# SevenSegment.net
KiCad netlist of a schematic drawn in Altium Designer
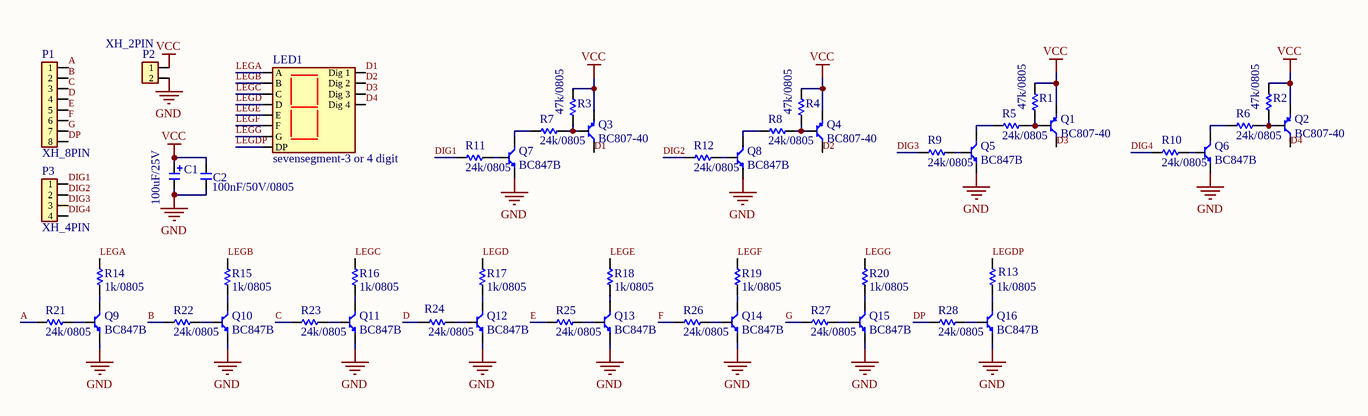
[diagram p0: SevenSegment.SchDoc]

(export (version "E")
  (design (tool "Eeschema 10.0.6"))
  (components
    (comp (ref "C1")
      (value "100uF/25V")
      (footprint "100uF/25V")
      (libsource (lib "SCHAM_LIB") (part "Capacitor-pol"))
    )
    (comp (ref "C2")
      (value "100nF/50V/0805")
      (footprint "Capacitor 0805")
      (libsource (lib "SCHAM_LIB") (part "capacitor"))
    )
    (comp (ref "LED1")
      (value "sevensegment-3 or 4 digit")
      (footprint "5631BS-7SEG")
      (libsource (lib "SCHAM_LIB") (part "sevensegment-3 or 4 digit"))
    )
    (comp (ref "P1")
      (value "XH_8PIN")
      (footprint "pin-header 8*1")
      (libsource (lib "SCHAM_LIB") (part "header 8pin"))
    )
    (comp (ref "P2")
      (value "XH_2PIN")
      (footprint "pin-header 2*1")
      (libsource (lib "SCHAM_LIB") (part "header 2pin"))
    )
    (comp (ref "P3")
      (value "XH_4PIN")
      (footprint "pin-header 4*1")
      (libsource (lib "SCHAM_LIB") (part "header 4pin"))
    )
    (comp (ref "Q1") (value "BC807-40") (footprint "SOT23") (libsource (lib "SCHAM_LIB") (part "bjt-pnp")))
    (comp (ref "Q2") (value "BC807-40") (footprint "SOT23") (libsource (lib "SCHAM_LIB") (part "bjt-pnp")))
    (comp (ref "Q3") (value "BC807-40") (footprint "SOT23") (libsource (lib "SCHAM_LIB") (part "bjt-pnp")))
    (comp (ref "Q4") (value "BC807-40") (footprint "SOT23") (libsource (lib "SCHAM_LIB") (part "bjt-pnp")))
    (comp (ref "Q5") (value "BC847B") (footprint "SOT23") (libsource (lib "SCHAM_LIB") (part "bjt-npn")))
    (comp (ref "Q6") (value "BC847B") (footprint "SOT23") (libsource (lib "SCHAM_LIB") (part "bjt-npn")))
    (comp (ref "Q7") (value "BC847B") (footprint "SOT23") (libsource (lib "SCHAM_LIB") (part "bjt-npn")))
    (comp (ref "Q8") (value "BC847B") (footprint "SOT23") (libsource (lib "SCHAM_LIB") (part "bjt-npn")))
    (comp (ref "Q9") (value "BC847B") (footprint "SOT23") (libsource (lib "SCHAM_LIB") (part "bjt-npn")))
    (comp (ref "Q10") (value "BC847B") (footprint "SOT23") (libsource (lib "SCHAM_LIB") (part "bjt-npn")))
    (comp (ref "Q11") (value "BC847B") (footprint "SOT23") (libsource (lib "SCHAM_LIB") (part "bjt-npn")))
    (comp (ref "Q12") (value "BC847B") (footprint "SOT23") (libsource (lib "SCHAM_LIB") (part "bjt-npn")))
    (comp (ref "Q13") (value "BC847B") (footprint "SOT23") (libsource (lib "SCHAM_LIB") (part "bjt-npn")))
    (comp (ref "Q14") (value "BC847B") (footprint "SOT23") (libsource (lib "SCHAM_LIB") (part "bjt-npn")))
    (comp (ref "Q15") (value "BC847B") (footprint "SOT23") (libsource (lib "SCHAM_LIB") (part "bjt-npn")))
    (comp (ref "Q16") (value "BC847B") (footprint "SOT23") (libsource (lib "SCHAM_LIB") (part "bjt-npn")))
    (comp (ref "R1")
      (value "47k/0805")
      (footprint "Resistor 0805")
      (libsource (lib "SCHAM_LIB") (part "resistor"))
    )
    (comp (ref "R2")
      (value "47k/0805")
      (footprint "Resistor 0805")
      (libsource (lib "SCHAM_LIB") (part "resistor"))
    )
    (comp (ref "R3")
      (value "47k/0805")
      (footprint "Resistor 0805")
      (libsource (lib "SCHAM_LIB") (part "resistor"))
    )
    (comp (ref "R4")
      (value "47k/0805")
      (footprint "Resistor 0805")
      (libsource (lib "SCHAM_LIB") (part "resistor"))
    )
    (comp (ref "R5")
      (value "24k/0805")
      (footprint "Resistor 0805")
      (libsource (lib "SCHAM_LIB") (part "resistor"))
    )
    (comp (ref "R6")
      (value "24k/0805")
      (footprint "Resistor 0805")
      (libsource (lib "SCHAM_LIB") (part "resistor"))
    )
    (comp (ref "R7")
      (value "24k/0805")
      (footprint "Resistor 0805")
      (libsource (lib "SCHAM_LIB") (part "resistor"))
    )
    (comp (ref "R8")
      (value "24k/0805")
      (footprint "Resistor 0805")
      (libsource (lib "SCHAM_LIB") (part "resistor"))
    )
    (comp (ref "R9")
      (value "24k/0805")
      (footprint "Resistor 0805")
      (libsource (lib "SCHAM_LIB") (part "resistor"))
    )
    (comp (ref "R10")
      (value "24k/0805")
      (footprint "Resistor 0805")
      (libsource (lib "SCHAM_LIB") (part "resistor"))
    )
    (comp (ref "R11")
      (value "24k/0805")
      (footprint "Resistor 0805")
      (libsource (lib "SCHAM_LIB") (part "resistor"))
    )
    (comp (ref "R12")
      (value "24k/0805")
      (footprint "Resistor 0805")
      (libsource (lib "SCHAM_LIB") (part "resistor"))
    )
    (comp (ref "R13")
      (value "1k/0805")
      (footprint "Resistor 0805")
      (libsource (lib "SCHAM_LIB") (part "resistor"))
    )
    (comp (ref "R14")
      (value "1k/0805")
      (footprint "Resistor 0805")
      (libsource (lib "SCHAM_LIB") (part "resistor"))
    )
    (comp (ref "R15")
      (value "1k/0805")
      (footprint "Resistor 0805")
      (libsource (lib "SCHAM_LIB") (part "resistor"))
    )
    (comp (ref "R16")
      (value "1k/0805")
      (footprint "Resistor 0805")
      (libsource (lib "SCHAM_LIB") (part "resistor"))
    )
    (comp (ref "R17")
      (value "1k/0805")
      (footprint "Resistor 0805")
      (libsource (lib "SCHAM_LIB") (part "resistor"))
    )
    (comp (ref "R18")
      (value "1k/0805")
      (footprint "Resistor 0805")
      (libsource (lib "SCHAM_LIB") (part "resistor"))
    )
    (comp (ref "R19")
      (value "1k/0805")
      (footprint "Resistor 0805")
      (libsource (lib "SCHAM_LIB") (part "resistor"))
    )
    (comp (ref "R20")
      (value "1k/0805")
      (footprint "Resistor 0805")
      (libsource (lib "SCHAM_LIB") (part "resistor"))
    )
    (comp (ref "R21")
      (value "24k/0805")
      (footprint "Resistor 0805")
      (libsource (lib "SCHAM_LIB") (part "resistor"))
    )
    (comp (ref "R22")
      (value "24k/0805")
      (footprint "Resistor 0805")
      (libsource (lib "SCHAM_LIB") (part "resistor"))
    )
    (comp (ref "R23")
      (value "24k/0805")
      (footprint "Resistor 0805")
      (libsource (lib "SCHAM_LIB") (part "resistor"))
    )
    (comp (ref "R24")
      (value "24k/0805")
      (footprint "Resistor 0805")
      (libsource (lib "SCHAM_LIB") (part "resistor"))
    )
    (comp (ref "R25")
      (value "24k/0805")
      (footprint "Resistor 0805")
      (libsource (lib "SCHAM_LIB") (part "resistor"))
    )
    (comp (ref "R26")
      (value "24k/0805")
      (footprint "Resistor 0805")
      (libsource (lib "SCHAM_LIB") (part "resistor"))
    )
    (comp (ref "R27")
      (value "24k/0805")
      (footprint "Resistor 0805")
      (libsource (lib "SCHAM_LIB") (part "resistor"))
    )
    (comp (ref "R28")
      (value "24k/0805")
      (footprint "Resistor 0805")
      (libsource (lib "SCHAM_LIB") (part "resistor"))
    )
  )
  (nets
    (net (code "1") (name "/A") (class "Default")
      (node (ref "P1") (pin "1") (pinfunction "1_1") (pintype "passive"))
      (node (ref "R21") (pin "2") (pinfunction "2_2") (pintype "passive"))
    )
    (net (code "2") (name "/B") (class "Default")
      (node (ref "P1") (pin "2") (pinfunction "2_2") (pintype "passive"))
      (node (ref "R22") (pin "2") (pinfunction "2_2") (pintype "passive"))
    )
    (net (code "3") (name "/C") (class "Default")
      (node (ref "P1") (pin "3") (pinfunction "3_3") (pintype "passive"))
      (node (ref "R23") (pin "2") (pinfunction "2_2") (pintype "passive"))
    )
    (net (code "4") (name "/D") (class "Default")
      (node (ref "P1") (pin "4") (pinfunction "4_4") (pintype "passive"))
      (node (ref "R24") (pin "2") (pinfunction "2_2") (pintype "passive"))
    )
    (net (code "5") (name "/D1") (class "Default")
      (node (ref "LED1") (pin "12") (pinfunction "Dig_1_12") (pintype "passive"))
      (node (ref "Q3") (pin "3") (pinfunction "C_3") (pintype "passive"))
    )
    (net (code "6") (name "/D2") (class "Default")
      (node (ref "LED1") (pin "9") (pinfunction "Dig_2_9") (pintype "passive"))
      (node (ref "Q4") (pin "3") (pinfunction "C_3") (pintype "passive"))
    )
    (net (code "7") (name "/D3") (class "Default")
      (node (ref "LED1") (pin "8") (pinfunction "Dig_3_8") (pintype "passive"))
      (node (ref "Q1") (pin "3") (pinfunction "C_3") (pintype "passive"))
    )
    (net (code "8") (name "/D4") (class "Default")
      (node (ref "LED1") (pin "6") (pinfunction "Dig_4_6") (pintype "passive"))
      (node (ref "Q2") (pin "3") (pinfunction "C_3") (pintype "passive"))
    )
    (net (code "9") (name "/DIG1") (class "Default")
      (node (ref "P3") (pin "1") (pinfunction "1_1") (pintype "passive"))
      (node (ref "R11") (pin "2") (pinfunction "2_2") (pintype "passive"))
    )
    (net (code "10") (name "/DIG2") (class "Default")
      (node (ref "P3") (pin "2") (pinfunction "2_2") (pintype "passive"))
      (node (ref "R12") (pin "2") (pinfunction "2_2") (pintype "passive"))
    )
    (net (code "11") (name "/DIG3") (class "Default")
      (node (ref "P3") (pin "3") (pinfunction "3_3") (pintype "passive"))
      (node (ref "R9") (pin "2") (pinfunction "2_2") (pintype "passive"))
    )
    (net (code "12") (name "/DIG4") (class "Default")
      (node (ref "P3") (pin "4") (pinfunction "4_4") (pintype "passive"))
      (node (ref "R10") (pin "2") (pinfunction "2_2") (pintype "passive"))
    )
    (net (code "13") (name "/DP") (class "Default")
      (node (ref "P1") (pin "8") (pinfunction "8_8") (pintype "passive"))
      (node (ref "R28") (pin "2") (pinfunction "2_2") (pintype "passive"))
    )
    (net (code "14") (name "/E") (class "Default")
      (node (ref "P1") (pin "5") (pinfunction "5_5") (pintype "passive"))
      (node (ref "R25") (pin "2") (pinfunction "2_2") (pintype "passive"))
    )
    (net (code "15") (name "/F") (class "Default")
      (node (ref "P1") (pin "6") (pinfunction "6_6") (pintype "passive"))
      (node (ref "R26") (pin "2") (pinfunction "2_2") (pintype "passive"))
    )
    (net (code "16") (name "/G") (class "Default")
      (node (ref "P1") (pin "7") (pinfunction "7_7") (pintype "passive"))
      (node (ref "R27") (pin "2") (pinfunction "2_2") (pintype "passive"))
    )
    (net (code "17") (name "/LEGA") (class "Default")
      (node (ref "LED1") (pin "11") (pinfunction "A_11") (pintype "passive"))
      (node (ref "R14") (pin "1") (pinfunction "1_1") (pintype "passive"))
    )
    (net (code "18") (name "/LEGB") (class "Default")
      (node (ref "LED1") (pin "7") (pinfunction "B_7") (pintype "passive"))
      (node (ref "R15") (pin "1") (pinfunction "1_1") (pintype "passive"))
    )
    (net (code "19") (name "/LEGC") (class "Default")
      (node (ref "LED1") (pin "4") (pinfunction "C_4") (pintype "passive"))
      (node (ref "R16") (pin "1") (pinfunction "1_1") (pintype "passive"))
    )
    (net (code "20") (name "/LEGD") (class "Default")
      (node (ref "LED1") (pin "2") (pinfunction "D_2") (pintype "passive"))
      (node (ref "R17") (pin "1") (pinfunction "1_1") (pintype "passive"))
    )
    (net (code "21") (name "/LEGDP") (class "Default")
      (node (ref "LED1") (pin "3") (pinfunction "DP_3") (pintype "passive"))
      (node (ref "R13") (pin "1") (pinfunction "1_1") (pintype "passive"))
    )
    (net (code "22") (name "/LEGE") (class "Default")
      (node (ref "LED1") (pin "1") (pinfunction "E_1") (pintype "passive"))
      (node (ref "R18") (pin "1") (pinfunction "1_1") (pintype "passive"))
    )
    (net (code "23") (name "/LEGF") (class "Default")
      (node (ref "LED1") (pin "10") (pinfunction "F_10") (pintype "passive"))
      (node (ref "R19") (pin "1") (pinfunction "1_1") (pintype "passive"))
    )
    (net (code "24") (name "/LEGG") (class "Default")
      (node (ref "LED1") (pin "5") (pinfunction "G_5") (pintype "passive"))
      (node (ref "R20") (pin "1") (pinfunction "1_1") (pintype "passive"))
    )
    (net (code "25") (name "GND") (class "Default")
      (node (ref "C1") (pin "2") (pinfunction "2_2") (pintype "passive"))
      (node (ref "C2") (pin "1") (pinfunction "1_1") (pintype "passive"))
      (node (ref "P2") (pin "2") (pinfunction "2_2") (pintype "passive"))
      (node (ref "Q10") (pin "2") (pinfunction "E_2") (pintype "passive"))
      (node (ref "Q11") (pin "2") (pinfunction "E_2") (pintype "passive"))
      (node (ref "Q12") (pin "2") (pinfunction "E_2") (pintype "passive"))
      (node (ref "Q13") (pin "2") (pinfunction "E_2") (pintype "passive"))
      (node (ref "Q14") (pin "2") (pinfunction "E_2") (pintype "passive"))
      (node (ref "Q15") (pin "2") (pinfunction "E_2") (pintype "passive"))
      (node (ref "Q16") (pin "2") (pinfunction "E_2") (pintype "passive"))
      (node (ref "Q5") (pin "2") (pinfunction "E_2") (pintype "passive"))
      (node (ref "Q6") (pin "2") (pinfunction "E_2") (pintype "passive"))
      (node (ref "Q7") (pin "2") (pinfunction "E_2") (pintype "passive"))
      (node (ref "Q8") (pin "2") (pinfunction "E_2") (pintype "passive"))
      (node (ref "Q9") (pin "2") (pinfunction "E_2") (pintype "passive"))
    )
    (net (code "26") (name "Net-(Q1-B)") (class "Default")
      (node (ref "Q1") (pin "1") (pinfunction "B_1") (pintype "passive"))
      (node (ref "R1") (pin "1") (pinfunction "1_1") (pintype "passive"))
      (node (ref "R5") (pin "2") (pinfunction "2_2") (pintype "passive"))
    )
    (net (code "27") (name "Net-(Q2-B)") (class "Default")
      (node (ref "Q2") (pin "1") (pinfunction "B_1") (pintype "passive"))
      (node (ref "R2") (pin "1") (pinfunction "1_1") (pintype "passive"))
      (node (ref "R6") (pin "2") (pinfunction "2_2") (pintype "passive"))
    )
    (net (code "28") (name "Net-(Q3-B)") (class "Default")
      (node (ref "Q3") (pin "1") (pinfunction "B_1") (pintype "passive"))
      (node (ref "R3") (pin "1") (pinfunction "1_1") (pintype "passive"))
      (node (ref "R7") (pin "2") (pinfunction "2_2") (pintype "passive"))
    )
    (net (code "29") (name "Net-(Q4-B)") (class "Default")
      (node (ref "Q4") (pin "1") (pinfunction "B_1") (pintype "passive"))
      (node (ref "R4") (pin "1") (pinfunction "1_1") (pintype "passive"))
      (node (ref "R8") (pin "2") (pinfunction "2_2") (pintype "passive"))
    )
    (net (code "30") (name "Net-(Q5-B)") (class "Default")
      (node (ref "Q5") (pin "1") (pinfunction "B_1") (pintype "passive"))
      (node (ref "R9") (pin "1") (pinfunction "1_1") (pintype "passive"))
    )
    (net (code "31") (name "Net-(Q5-C)") (class "Default")
      (node (ref "Q5") (pin "3") (pinfunction "C_3") (pintype "passive"))
      (node (ref "R5") (pin "1") (pinfunction "1_1") (pintype "passive"))
    )
    (net (code "32") (name "Net-(Q6-B)") (class "Default")
      (node (ref "Q6") (pin "1") (pinfunction "B_1") (pintype "passive"))
      (node (ref "R10") (pin "1") (pinfunction "1_1") (pintype "passive"))
    )
    (net (code "33") (name "Net-(Q6-C)") (class "Default")
      (node (ref "Q6") (pin "3") (pinfunction "C_3") (pintype "passive"))
      (node (ref "R6") (pin "1") (pinfunction "1_1") (pintype "passive"))
    )
    (net (code "34") (name "Net-(Q7-B)") (class "Default")
      (node (ref "Q7") (pin "1") (pinfunction "B_1") (pintype "passive"))
      (node (ref "R11") (pin "1") (pinfunction "1_1") (pintype "passive"))
    )
    (net (code "35") (name "Net-(Q7-C)") (class "Default")
      (node (ref "Q7") (pin "3") (pinfunction "C_3") (pintype "passive"))
      (node (ref "R7") (pin "1") (pinfunction "1_1") (pintype "passive"))
    )
    (net (code "36") (name "Net-(Q8-B)") (class "Default")
      (node (ref "Q8") (pin "1") (pinfunction "B_1") (pintype "passive"))
      (node (ref "R12") (pin "1") (pinfunction "1_1") (pintype "passive"))
    )
    (net (code "37") (name "Net-(Q8-C)") (class "Default")
      (node (ref "Q8") (pin "3") (pinfunction "C_3") (pintype "passive"))
      (node (ref "R8") (pin "1") (pinfunction "1_1") (pintype "passive"))
    )
    (net (code "38") (name "Net-(Q9-B)") (class "Default")
      (node (ref "Q9") (pin "1") (pinfunction "B_1") (pintype "passive"))
      (node (ref "R21") (pin "1") (pinfunction "1_1") (pintype "passive"))
    )
    (net (code "39") (name "Net-(Q9-C)") (class "Default")
      (node (ref "Q9") (pin "3") (pinfunction "C_3") (pintype "passive"))
      (node (ref "R14") (pin "2") (pinfunction "2_2") (pintype "passive"))
    )
    (net (code "40") (name "Net-(Q10-B)") (class "Default")
      (node (ref "Q10") (pin "1") (pinfunction "B_1") (pintype "passive"))
      (node (ref "R22") (pin "1") (pinfunction "1_1") (pintype "passive"))
    )
    (net (code "41") (name "Net-(Q10-C)") (class "Default")
      (node (ref "Q10") (pin "3") (pinfunction "C_3") (pintype "passive"))
      (node (ref "R15") (pin "2") (pinfunction "2_2") (pintype "passive"))
    )
    (net (code "42") (name "Net-(Q11-B)") (class "Default")
      (node (ref "Q11") (pin "1") (pinfunction "B_1") (pintype "passive"))
      (node (ref "R23") (pin "1") (pinfunction "1_1") (pintype "passive"))
    )
    (net (code "43") (name "Net-(Q11-C)") (class "Default")
      (node (ref "Q11") (pin "3") (pinfunction "C_3") (pintype "passive"))
      (node (ref "R16") (pin "2") (pinfunction "2_2") (pintype "passive"))
    )
    (net (code "44") (name "Net-(Q12-B)") (class "Default")
      (node (ref "Q12") (pin "1") (pinfunction "B_1") (pintype "passive"))
      (node (ref "R24") (pin "1") (pinfunction "1_1") (pintype "passive"))
    )
    (net (code "45") (name "Net-(Q12-C)") (class "Default")
      (node (ref "Q12") (pin "3") (pinfunction "C_3") (pintype "passive"))
      (node (ref "R17") (pin "2") (pinfunction "2_2") (pintype "passive"))
    )
    (net (code "46") (name "Net-(Q13-B)") (class "Default")
      (node (ref "Q13") (pin "1") (pinfunction "B_1") (pintype "passive"))
      (node (ref "R25") (pin "1") (pinfunction "1_1") (pintype "passive"))
    )
    (net (code "47") (name "Net-(Q13-C)") (class "Default")
      (node (ref "Q13") (pin "3") (pinfunction "C_3") (pintype "passive"))
      (node (ref "R18") (pin "2") (pinfunction "2_2") (pintype "passive"))
    )
    (net (code "48") (name "Net-(Q14-B)") (class "Default")
      (node (ref "Q14") (pin "1") (pinfunction "B_1") (pintype "passive"))
      (node (ref "R26") (pin "1") (pinfunction "1_1") (pintype "passive"))
    )
    (net (code "49") (name "Net-(Q14-C)") (class "Default")
      (node (ref "Q14") (pin "3") (pinfunction "C_3") (pintype "passive"))
      (node (ref "R19") (pin "2") (pinfunction "2_2") (pintype "passive"))
    )
    (net (code "50") (name "Net-(Q15-B)") (class "Default")
      (node (ref "Q15") (pin "1") (pinfunction "B_1") (pintype "passive"))
      (node (ref "R27") (pin "1") (pinfunction "1_1") (pintype "passive"))
    )
    (net (code "51") (name "Net-(Q15-C)") (class "Default")
      (node (ref "Q15") (pin "3") (pinfunction "C_3") (pintype "passive"))
      (node (ref "R20") (pin "2") (pinfunction "2_2") (pintype "passive"))
    )
    (net (code "52") (name "Net-(Q16-B)") (class "Default")
      (node (ref "Q16") (pin "1") (pinfunction "B_1") (pintype "passive"))
      (node (ref "R28") (pin "1") (pinfunction "1_1") (pintype "passive"))
    )
    (net (code "53") (name "Net-(Q16-C)") (class "Default")
      (node (ref "Q16") (pin "3") (pinfunction "C_3") (pintype "passive"))
      (node (ref "R13") (pin "2") (pinfunction "2_2") (pintype "passive"))
    )
    (net (code "54") (name "VCC") (class "Default")
      (node (ref "C1") (pin "1") (pinfunction "1_1") (pintype "passive"))
      (node (ref "C2") (pin "2") (pinfunction "2_2") (pintype "passive"))
      (node (ref "P2") (pin "1") (pinfunction "1_1") (pintype "passive"))
      (node (ref "Q1") (pin "2") (pinfunction "E_2") (pintype "passive"))
      (node (ref "Q2") (pin "2") (pinfunction "E_2") (pintype "passive"))
      (node (ref "Q3") (pin "2") (pinfunction "E_2") (pintype "passive"))
      (node (ref "Q4") (pin "2") (pinfunction "E_2") (pintype "passive"))
      (node (ref "R1") (pin "2") (pinfunction "2_2") (pintype "passive"))
      (node (ref "R2") (pin "2") (pinfunction "2_2") (pintype "passive"))
      (node (ref "R3") (pin "2") (pinfunction "2_2") (pintype "passive"))
      (node (ref "R4") (pin "2") (pinfunction "2_2") (pintype "passive"))
    )
  )
)
